# relay_shield_v1.net
KiCad netlist of a schematic drawn in EAGLE
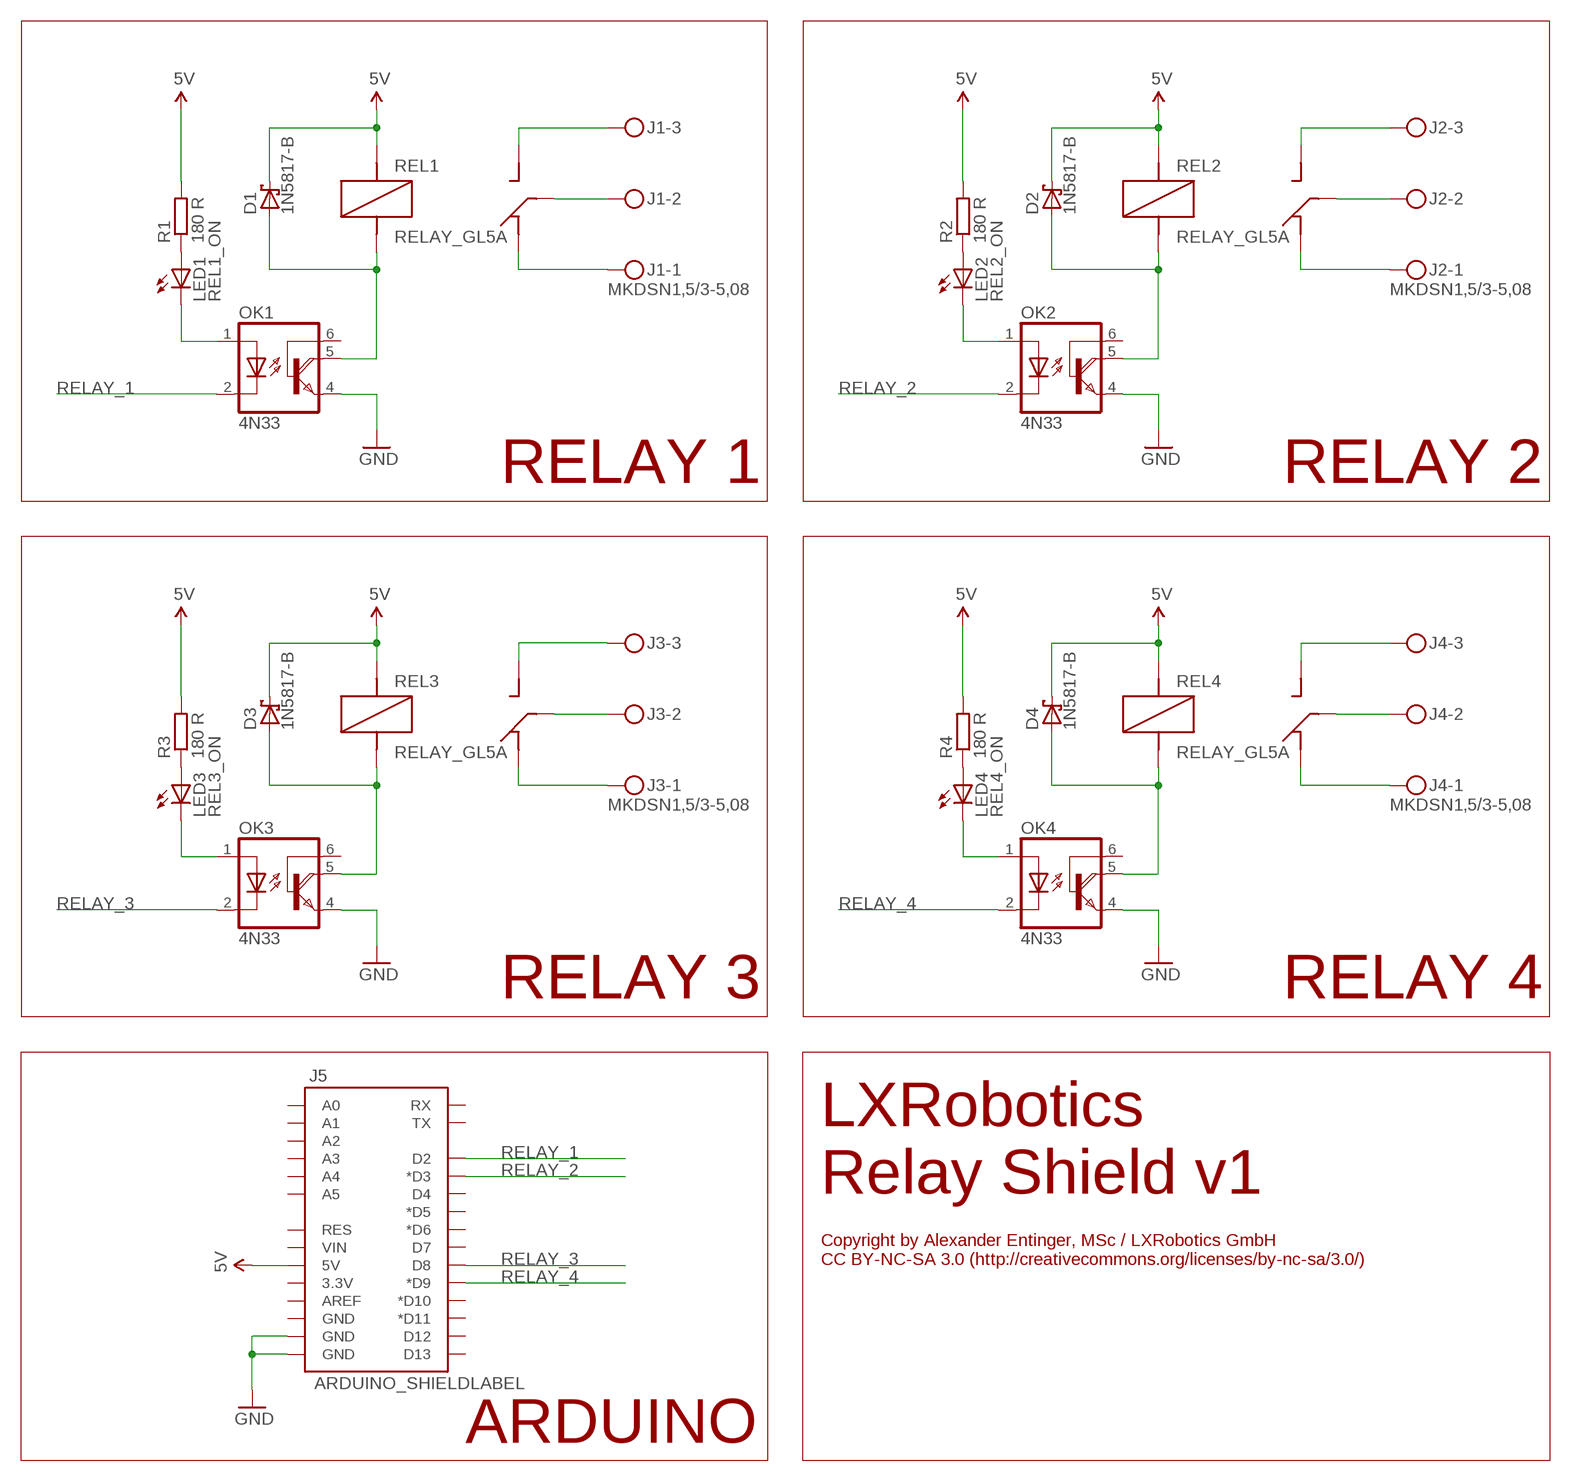
[diagram p0: schematic, sheet 1]

(export (version "E")
  (design (tool "Eeschema 10.0.6"))
  (components
    (comp (ref "D1")
      (value "1N5817-B")
      (footprint "eagle-import:DO41-7.6")
      (libsource (lib "eagle-import") (part "1N5817-B"))
    )
    (comp (ref "D2")
      (value "1N5817-B")
      (footprint "eagle-import:DO41-7.6")
      (libsource (lib "eagle-import") (part "1N5817-B"))
    )
    (comp (ref "D3")
      (value "1N5817-B")
      (footprint "eagle-import:DO41-7.6")
      (libsource (lib "eagle-import") (part "1N5817-B"))
    )
    (comp (ref "D4")
      (value "1N5817-B")
      (footprint "eagle-import:DO41-7.6")
      (libsource (lib "eagle-import") (part "1N5817-B"))
    )
    (comp (ref "J1")
      (value "MKDSN1,5/3-5,08")
      (footprint "eagle-import:MKDSN1,5_3-5,08")
      (fields (field (name "MPN") "SMKDSN1,5/3-5,08"))
      (libsource (lib "eagle-import") (part "MKDSN1,5/3-5,08"))
    )
    (comp (ref "J2")
      (value "MKDSN1,5/3-5,08")
      (footprint "eagle-import:MKDSN1,5_3-5,08")
      (fields (field (name "MPN") "SMKDSN1,5/3-5,08"))
      (libsource (lib "eagle-import") (part "MKDSN1,5/3-5,08"))
    )
    (comp (ref "J3")
      (value "MKDSN1,5/3-5,08")
      (footprint "eagle-import:MKDSN1,5_3-5,08")
      (fields (field (name "MPN") "SMKDSN1,5/3-5,08"))
      (libsource (lib "eagle-import") (part "MKDSN1,5/3-5,08"))
    )
    (comp (ref "J4")
      (value "MKDSN1,5/3-5,08")
      (footprint "eagle-import:MKDSN1,5_3-5,08")
      (fields (field (name "MPN") "SMKDSN1,5/3-5,08"))
      (libsource (lib "eagle-import") (part "MKDSN1,5/3-5,08"))
    )
    (comp (ref "J5")
      (value "ARDUINO_SHIELDLABEL")
      (footprint "eagle-import:DUEMILANOVE_SHIELD")
      (libsource (lib "eagle-import") (part "ARDUINO_SHIELDLABEL"))
    )
    (comp (ref "LED1")
      (value "REL1_ON")
      (footprint "eagle-import:LED5MM")
      (libsource (lib "eagle-import") (part "LED5MM"))
    )
    (comp (ref "LED2")
      (value "REL2_ON")
      (footprint "eagle-import:LED5MM")
      (libsource (lib "eagle-import") (part "LED5MM"))
    )
    (comp (ref "LED3")
      (value "REL3_ON")
      (footprint "eagle-import:LED5MM")
      (libsource (lib "eagle-import") (part "LED5MM"))
    )
    (comp (ref "LED4")
      (value "REL4_ON")
      (footprint "eagle-import:LED5MM")
      (libsource (lib "eagle-import") (part "LED5MM"))
    )
    (comp (ref "OK1")
      (value "4N33")
      (footprint "eagle-import:DIL06")
      (fields (field (name "MF") "VISHAY/TELEFUNKEN"))
      (libsource (lib "eagle-import") (part "4N33"))
    )
    (comp (ref "OK2")
      (value "4N33")
      (footprint "eagle-import:DIL06")
      (fields (field (name "MF") "VISHAY/TELEFUNKEN"))
      (libsource (lib "eagle-import") (part "4N33"))
    )
    (comp (ref "OK3")
      (value "4N33")
      (footprint "eagle-import:DIL06")
      (fields (field (name "MF") "VISHAY/TELEFUNKEN"))
      (libsource (lib "eagle-import") (part "4N33"))
    )
    (comp (ref "OK4")
      (value "4N33")
      (footprint "eagle-import:DIL06")
      (fields (field (name "MF") "VISHAY/TELEFUNKEN"))
      (libsource (lib "eagle-import") (part "4N33"))
    )
    (comp (ref "R1")
      (value "180 R")
      (footprint "eagle-import:0204_7")
      (libsource (lib "eagle-import") (part "R-EU_0204/7"))
    )
    (comp (ref "R2")
      (value "180 R")
      (footprint "eagle-import:0204_7")
      (libsource (lib "eagle-import") (part "R-EU_0204/7"))
    )
    (comp (ref "R3")
      (value "180 R")
      (footprint "eagle-import:0204_7")
      (libsource (lib "eagle-import") (part "R-EU_0204/7"))
    )
    (comp (ref "R4")
      (value "180 R")
      (footprint "eagle-import:0204_7")
      (libsource (lib "eagle-import") (part "R-EU_0204/7"))
    )
    (comp (ref "REL1")
      (value "RELAY_GL5A")
      (footprint "eagle-import:RELAY_GL5A")
      (libsource (lib "eagle-import") (part "RELAY_GL5A"))
    )
    (comp (ref "REL2")
      (value "RELAY_GL5A")
      (footprint "eagle-import:RELAY_GL5A")
      (libsource (lib "eagle-import") (part "RELAY_GL5A"))
    )
    (comp (ref "REL3")
      (value "RELAY_GL5A")
      (footprint "eagle-import:RELAY_GL5A")
      (libsource (lib "eagle-import") (part "RELAY_GL5A"))
    )
    (comp (ref "REL4")
      (value "RELAY_GL5A")
      (footprint "eagle-import:RELAY_GL5A")
      (libsource (lib "eagle-import") (part "RELAY_GL5A"))
    )
  )
  (nets
    (net (code "1") (name "/RELAY_1") (class "Default")
      (node (ref "J5") (pin "D2") (pinfunction "D2_D2") (pintype "bidirectional"))
      (node (ref "OK1") (pin "2") (pinfunction "C_2") (pintype "passive"))
    )
    (net (code "2") (name "/RELAY_2") (class "Default")
      (node (ref "J5") (pin "D3") (pinfunction "*D3_D3") (pintype "bidirectional"))
      (node (ref "OK2") (pin "2") (pinfunction "C_2") (pintype "passive"))
    )
    (net (code "3") (name "/RELAY_3") (class "Default")
      (node (ref "J5") (pin "D8") (pinfunction "D8_D8") (pintype "bidirectional"))
      (node (ref "OK3") (pin "2") (pinfunction "C_2") (pintype "passive"))
    )
    (net (code "4") (name "/RELAY_4") (class "Default")
      (node (ref "J5") (pin "D9") (pinfunction "*D9_D9") (pintype "bidirectional"))
      (node (ref "OK4") (pin "2") (pinfunction "C_2") (pintype "passive"))
    )
    (net (code "5") (name "5V") (class "Default")
      (node (ref "D1") (pin "C") (pinfunction "C_C") (pintype "passive"))
      (node (ref "D2") (pin "C") (pinfunction "C_C") (pintype "passive"))
      (node (ref "D3") (pin "C") (pinfunction "C_C") (pintype "passive"))
      (node (ref "D4") (pin "C") (pinfunction "C_C") (pintype "passive"))
      (node (ref "J5") (pin "5V") (pinfunction "5V_5V") (pintype "bidirectional"))
      (node (ref "R1") (pin "2") (pinfunction "2_2") (pintype "passive"))
      (node (ref "R2") (pin "2") (pinfunction "2_2") (pintype "passive"))
      (node (ref "R3") (pin "2") (pinfunction "2_2") (pintype "passive"))
      (node (ref "R4") (pin "2") (pinfunction "2_2") (pintype "passive"))
      (node (ref "REL1") (pin "R2") (pinfunction "R2_COIL1_R2") (pintype "bidirectional"))
      (node (ref "REL2") (pin "R2") (pinfunction "R2_COIL1_R2") (pintype "bidirectional"))
      (node (ref "REL3") (pin "R2") (pinfunction "R2_COIL1_R2") (pintype "bidirectional"))
      (node (ref "REL4") (pin "R2") (pinfunction "R2_COIL1_R2") (pintype "bidirectional"))
    )
    (net (code "6") (name "GND") (class "Default")
      (node (ref "J5") (pin "GND@0") (pinfunction "GND_GND@0") (pintype "bidirectional"))
      (node (ref "J5") (pin "GND@1") (pinfunction "GND_GND@1") (pintype "bidirectional"))
      (node (ref "OK1") (pin "4") (pinfunction "E_4") (pintype "passive"))
      (node (ref "OK2") (pin "4") (pinfunction "E_4") (pintype "passive"))
      (node (ref "OK3") (pin "4") (pinfunction "E_4") (pintype "passive"))
      (node (ref "OK4") (pin "4") (pinfunction "E_4") (pintype "passive"))
    )
    (net (code "7") (name "Net-(J1A-KL)") (class "Default")
      (node (ref "J1") (pin "1") (pinfunction "KL_1") (pintype "passive"))
      (node (ref "REL1") (pin "R4") (pinfunction "R4_SW_R4") (pintype "bidirectional"))
    )
    (net (code "8") (name "Net-(J1B-KL)") (class "Default")
      (node (ref "J1") (pin "2") (pinfunction "KL_2") (pintype "passive"))
      (node (ref "REL1") (pin "R1") (pinfunction "R1_COMMON_R1") (pintype "bidirectional"))
    )
    (net (code "9") (name "Net-(J1C-KL)") (class "Default")
      (node (ref "J1") (pin "3") (pinfunction "KL_3") (pintype "passive"))
      (node (ref "REL1") (pin "R3") (pinfunction "R3_SW_R3") (pintype "bidirectional"))
    )
    (net (code "10") (name "Net-(J2A-KL)") (class "Default")
      (node (ref "J2") (pin "1") (pinfunction "KL_1") (pintype "passive"))
      (node (ref "REL2") (pin "R4") (pinfunction "R4_SW_R4") (pintype "bidirectional"))
    )
    (net (code "11") (name "Net-(J2B-KL)") (class "Default")
      (node (ref "J2") (pin "2") (pinfunction "KL_2") (pintype "passive"))
      (node (ref "REL2") (pin "R1") (pinfunction "R1_COMMON_R1") (pintype "bidirectional"))
    )
    (net (code "12") (name "Net-(J2C-KL)") (class "Default")
      (node (ref "J2") (pin "3") (pinfunction "KL_3") (pintype "passive"))
      (node (ref "REL2") (pin "R3") (pinfunction "R3_SW_R3") (pintype "bidirectional"))
    )
    (net (code "13") (name "Net-(J3A-KL)") (class "Default")
      (node (ref "J3") (pin "1") (pinfunction "KL_1") (pintype "passive"))
      (node (ref "REL3") (pin "R4") (pinfunction "R4_SW_R4") (pintype "bidirectional"))
    )
    (net (code "14") (name "Net-(J3B-KL)") (class "Default")
      (node (ref "J3") (pin "2") (pinfunction "KL_2") (pintype "passive"))
      (node (ref "REL3") (pin "R1") (pinfunction "R1_COMMON_R1") (pintype "bidirectional"))
    )
    (net (code "15") (name "Net-(J3C-KL)") (class "Default")
      (node (ref "J3") (pin "3") (pinfunction "KL_3") (pintype "passive"))
      (node (ref "REL3") (pin "R3") (pinfunction "R3_SW_R3") (pintype "bidirectional"))
    )
    (net (code "16") (name "Net-(J4A-KL)") (class "Default")
      (node (ref "J4") (pin "1") (pinfunction "KL_1") (pintype "passive"))
      (node (ref "REL4") (pin "R4") (pinfunction "R4_SW_R4") (pintype "bidirectional"))
    )
    (net (code "17") (name "Net-(J4B-KL)") (class "Default")
      (node (ref "J4") (pin "2") (pinfunction "KL_2") (pintype "passive"))
      (node (ref "REL4") (pin "R1") (pinfunction "R1_COMMON_R1") (pintype "bidirectional"))
    )
    (net (code "18") (name "Net-(J4C-KL)") (class "Default")
      (node (ref "J4") (pin "3") (pinfunction "KL_3") (pintype "passive"))
      (node (ref "REL4") (pin "R3") (pinfunction "R3_SW_R3") (pintype "bidirectional"))
    )
    (net (code "19") (name "Net-(LED1-C)") (class "Default")
      (node (ref "LED1") (pin "K") (pinfunction "C_K") (pintype "passive"))
      (node (ref "OK1") (pin "1") (pinfunction "A_1") (pintype "passive"))
    )
    (net (code "20") (name "Net-(LED1-PadA)") (class "Default")
      (node (ref "LED1") (pin "A") (pinfunction "A_A") (pintype "passive"))
      (node (ref "R1") (pin "1") (pinfunction "1_1") (pintype "passive"))
    )
    (net (code "21") (name "Net-(LED2-C)") (class "Default")
      (node (ref "LED2") (pin "K") (pinfunction "C_K") (pintype "passive"))
      (node (ref "OK2") (pin "1") (pinfunction "A_1") (pintype "passive"))
    )
    (net (code "22") (name "Net-(LED2-PadA)") (class "Default")
      (node (ref "LED2") (pin "A") (pinfunction "A_A") (pintype "passive"))
      (node (ref "R2") (pin "1") (pinfunction "1_1") (pintype "passive"))
    )
    (net (code "23") (name "Net-(LED3-C)") (class "Default")
      (node (ref "LED3") (pin "K") (pinfunction "C_K") (pintype "passive"))
      (node (ref "OK3") (pin "1") (pinfunction "A_1") (pintype "passive"))
    )
    (net (code "24") (name "Net-(LED3-PadA)") (class "Default")
      (node (ref "LED3") (pin "A") (pinfunction "A_A") (pintype "passive"))
      (node (ref "R3") (pin "1") (pinfunction "1_1") (pintype "passive"))
    )
    (net (code "25") (name "Net-(LED4-C)") (class "Default")
      (node (ref "LED4") (pin "K") (pinfunction "C_K") (pintype "passive"))
      (node (ref "OK4") (pin "1") (pinfunction "A_1") (pintype "passive"))
    )
    (net (code "26") (name "Net-(LED4-PadA)") (class "Default")
      (node (ref "LED4") (pin "A") (pinfunction "A_A") (pintype "passive"))
      (node (ref "R4") (pin "1") (pinfunction "1_1") (pintype "passive"))
    )
    (net (code "27") (name "Net-(OK1-COL)") (class "Default")
      (node (ref "D1") (pin "A") (pinfunction "A_A") (pintype "passive"))
      (node (ref "OK1") (pin "5") (pinfunction "COL_5") (pintype "passive"))
      (node (ref "REL1") (pin "R5") (pinfunction "R5_COIL2_R5") (pintype "bidirectional"))
    )
    (net (code "28") (name "Net-(OK2-COL)") (class "Default")
      (node (ref "D2") (pin "A") (pinfunction "A_A") (pintype "passive"))
      (node (ref "OK2") (pin "5") (pinfunction "COL_5") (pintype "passive"))
      (node (ref "REL2") (pin "R5") (pinfunction "R5_COIL2_R5") (pintype "bidirectional"))
    )
    (net (code "29") (name "Net-(OK3-COL)") (class "Default")
      (node (ref "D3") (pin "A") (pinfunction "A_A") (pintype "passive"))
      (node (ref "OK3") (pin "5") (pinfunction "COL_5") (pintype "passive"))
      (node (ref "REL3") (pin "R5") (pinfunction "R5_COIL2_R5") (pintype "bidirectional"))
    )
    (net (code "30") (name "Net-(OK4-COL)") (class "Default")
      (node (ref "D4") (pin "A") (pinfunction "A_A") (pintype "passive"))
      (node (ref "OK4") (pin "5") (pinfunction "COL_5") (pintype "passive"))
      (node (ref "REL4") (pin "R5") (pinfunction "R5_COIL2_R5") (pintype "bidirectional"))
    )
    (net (code "31") (name "unconnected-(J5-*D5-PadD5)") (class "Default")
      (node (ref "J5") (pin "D5") (pinfunction "*D5_D5") (pintype "bidirectional"))
    )
    (net (code "32") (name "unconnected-(J5-*D6-PadD6)") (class "Default")
      (node (ref "J5") (pin "D6") (pinfunction "*D6_D6") (pintype "bidirectional"))
    )
    (net (code "33") (name "unconnected-(J5-*D10-PadD10)") (class "Default")
      (node (ref "J5") (pin "D10") (pinfunction "*D10_D10") (pintype "bidirectional"))
    )
    (net (code "34") (name "unconnected-(J5-*D11-PadD11)") (class "Default")
      (node (ref "J5") (pin "D11") (pinfunction "*D11_D11") (pintype "bidirectional"))
    )
    (net (code "35") (name "unconnected-(J5-GND-PadGND@2)") (class "Default")
      (node (ref "J5") (pin "GND@2") (pinfunction "GND_GND@2") (pintype "bidirectional"))
    )
    (net (code "36") (name "unconnected-(J5-Pad3.3V)") (class "Default")
      (node (ref "J5") (pin "3.3V") (pinfunction "3.3V_3.3V") (pintype "bidirectional"))
    )
    (net (code "37") (name "unconnected-(J5-PadA0)") (class "Default")
      (node (ref "J5") (pin "A0") (pinfunction "A0_A0") (pintype "bidirectional"))
    )
    (net (code "38") (name "unconnected-(J5-PadA1)") (class "Default")
      (node (ref "J5") (pin "A1") (pinfunction "A1_A1") (pintype "bidirectional"))
    )
    (net (code "39") (name "unconnected-(J5-PadA2)") (class "Default")
      (node (ref "J5") (pin "A2") (pinfunction "A2_A2") (pintype "bidirectional"))
    )
    (net (code "40") (name "unconnected-(J5-PadA3)") (class "Default")
      (node (ref "J5") (pin "A3") (pinfunction "A3_A3") (pintype "bidirectional"))
    )
    (net (code "41") (name "unconnected-(J5-PadA4)") (class "Default")
      (node (ref "J5") (pin "A4") (pinfunction "A4_A4") (pintype "bidirectional"))
    )
    (net (code "42") (name "unconnected-(J5-PadA5)") (class "Default")
      (node (ref "J5") (pin "A5") (pinfunction "A5_A5") (pintype "bidirectional"))
    )
    (net (code "43") (name "unconnected-(J5-PadAREF)") (class "Default")
      (node (ref "J5") (pin "AREF") (pinfunction "AREF_AREF") (pintype "bidirectional"))
    )
    (net (code "44") (name "unconnected-(J5-PadD4)") (class "Default")
      (node (ref "J5") (pin "D4") (pinfunction "D4_D4") (pintype "bidirectional"))
    )
    (net (code "45") (name "unconnected-(J5-PadD7)") (class "Default")
      (node (ref "J5") (pin "D7") (pinfunction "D7_D7") (pintype "bidirectional"))
    )
    (net (code "46") (name "unconnected-(J5-PadD12)") (class "Default")
      (node (ref "J5") (pin "D12") (pinfunction "D12_D12") (pintype "bidirectional"))
    )
    (net (code "47") (name "unconnected-(J5-PadD13)") (class "Default")
      (node (ref "J5") (pin "D13") (pinfunction "D13_D13") (pintype "bidirectional"))
    )
    (net (code "48") (name "unconnected-(J5-PadRES)") (class "Default")
      (node (ref "J5") (pin "RES") (pinfunction "RES_RES") (pintype "bidirectional"))
    )
    (net (code "49") (name "unconnected-(J5-PadRX)") (class "Default")
      (node (ref "J5") (pin "RX") (pinfunction "RX_RX") (pintype "bidirectional"))
    )
    (net (code "50") (name "unconnected-(J5-PadTX)") (class "Default")
      (node (ref "J5") (pin "TX") (pinfunction "TX_TX") (pintype "bidirectional"))
    )
    (net (code "51") (name "unconnected-(J5-PadVIN)") (class "Default")
      (node (ref "J5") (pin "VIN") (pinfunction "VIN_VIN") (pintype "bidirectional"))
    )
    (net (code "52") (name "unconnected-(OK1-B-Pad6)") (class "Default")
      (node (ref "OK1") (pin "6") (pinfunction "B_6") (pintype "passive"))
    )
    (net (code "53") (name "unconnected-(OK2-B-Pad6)") (class "Default")
      (node (ref "OK2") (pin "6") (pinfunction "B_6") (pintype "passive"))
    )
    (net (code "54") (name "unconnected-(OK3-B-Pad6)") (class "Default")
      (node (ref "OK3") (pin "6") (pinfunction "B_6") (pintype "passive"))
    )
    (net (code "55") (name "unconnected-(OK4-B-Pad6)") (class "Default")
      (node (ref "OK4") (pin "6") (pinfunction "B_6") (pintype "passive"))
    )
  )
)
